# Connector_Exp.net
KiCad netlist of a schematic drawn in EAGLE
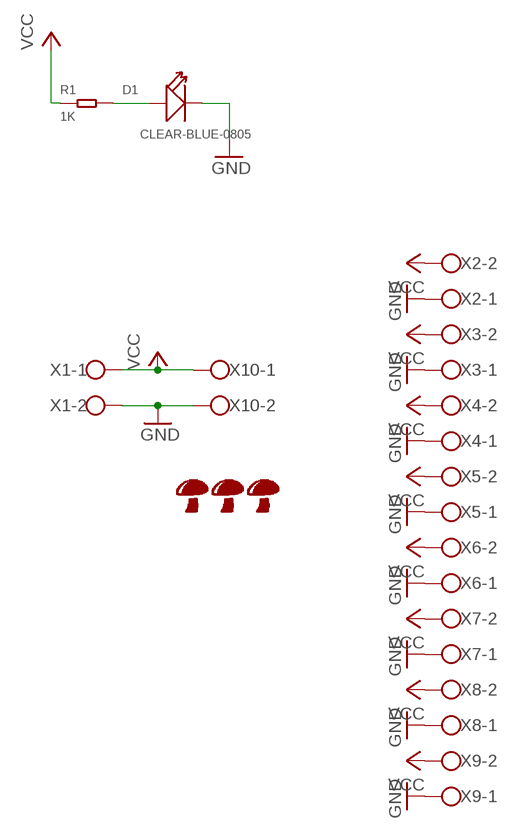
[diagram p0: schematic, sheet 1]

(export (version "E")
  (design (tool "Eeschema 10.0.6"))
  (components
    (comp (ref "D1")
      (value "CLEAR-BLUE-0805")
      (footprint "eagle-import:LED-0805")
      (fields (field (name "MPN") "EL-17-215/BHC-AN1P2/3T"))
      (libsource (lib "eagle-import") (part "SMD-LED-CLEAR-BLUE(0805)"))
    )
    (comp (ref "R1")
      (value "1K")
      (footprint "eagle-import:R0805")
      (fields (field (name "MPN") "RC0805JR-071KL"))
      (libsource (lib "eagle-import") (part "SMD-RES-1K-5%-1/8W(0805)"))
    )
    (comp (ref "U$1")
      (value "SHROOMTOPSILK")
      (footprint "eagle-import:SHROOM_TS")
      (libsource (lib "eagle-import") (part "SHROOMTOPSILK"))
    )
    (comp (ref "U$2")
      (value "SHROOMBOTTOMSILK")
      (footprint "eagle-import:SHROOM_BS")
      (libsource (lib "eagle-import") (part "SHROOMBOTTOMSILK"))
    )
    (comp (ref "U$3")
      (value "SHROOM10MM")
      (footprint "eagle-import:SHROOM10MM")
      (libsource (lib "eagle-import") (part "SHROOM10MM"))
    )
    (comp (ref "X1")
      (value "W237-102")
      (footprint "eagle-import:W237-102")
      (fields (field (name "MPN") "237-102"))
      (libsource (lib "eagle-import") (part "W237-102"))
    )
    (comp (ref "X2")
      (value "W237-102")
      (footprint "eagle-import:W237-102")
      (fields (field (name "MPN") "237-102"))
      (libsource (lib "eagle-import") (part "W237-102"))
    )
    (comp (ref "X3")
      (value "W237-102")
      (footprint "eagle-import:W237-102")
      (fields (field (name "MPN") "237-102"))
      (libsource (lib "eagle-import") (part "W237-102"))
    )
    (comp (ref "X4")
      (value "W237-102")
      (footprint "eagle-import:W237-102")
      (fields (field (name "MPN") "237-102"))
      (libsource (lib "eagle-import") (part "W237-102"))
    )
    (comp (ref "X5")
      (value "W237-102")
      (footprint "eagle-import:W237-102")
      (fields (field (name "MPN") "237-102"))
      (libsource (lib "eagle-import") (part "W237-102"))
    )
    (comp (ref "X6")
      (value "W237-102")
      (footprint "eagle-import:W237-102")
      (fields (field (name "MPN") "237-102"))
      (libsource (lib "eagle-import") (part "W237-102"))
    )
    (comp (ref "X7")
      (value "W237-102")
      (footprint "eagle-import:W237-102")
      (fields (field (name "MPN") "237-102"))
      (libsource (lib "eagle-import") (part "W237-102"))
    )
    (comp (ref "X8")
      (value "W237-102")
      (footprint "eagle-import:W237-102")
      (fields (field (name "MPN") "237-102"))
      (libsource (lib "eagle-import") (part "W237-102"))
    )
    (comp (ref "X9")
      (value "W237-102")
      (footprint "eagle-import:W237-102")
      (fields (field (name "MPN") "237-102"))
      (libsource (lib "eagle-import") (part "W237-102"))
    )
    (comp (ref "X10")
      (value "W237-102")
      (footprint "eagle-import:W237-102")
      (fields (field (name "MPN") "237-102"))
      (libsource (lib "eagle-import") (part "W237-102"))
    )
  )
  (nets
    (net (code "1") (name "GND") (class "Default")
      (node (ref "D1") (pin "-") (pinfunction "-_-") (pintype "passive"))
      (node (ref "X1") (pin "2") (pinfunction "KL_2") (pintype "passive"))
      (node (ref "X10") (pin "2") (pinfunction "KL_2") (pintype "passive"))
      (node (ref "X2") (pin "1") (pinfunction "KL_1") (pintype "passive"))
      (node (ref "X3") (pin "1") (pinfunction "KL_1") (pintype "passive"))
      (node (ref "X4") (pin "1") (pinfunction "KL_1") (pintype "passive"))
      (node (ref "X5") (pin "1") (pinfunction "KL_1") (pintype "passive"))
      (node (ref "X6") (pin "1") (pinfunction "KL_1") (pintype "passive"))
      (node (ref "X7") (pin "1") (pinfunction "KL_1") (pintype "passive"))
      (node (ref "X8") (pin "1") (pinfunction "KL_1") (pintype "passive"))
      (node (ref "X9") (pin "1") (pinfunction "KL_1") (pintype "passive"))
    )
    (net (code "2") (name "Net-(D1-Pad+)") (class "Default")
      (node (ref "D1") (pin "+") (pinfunction "+_+") (pintype "passive"))
      (node (ref "R1") (pin "2") (pinfunction "2_2") (pintype "passive"))
    )
    (net (code "3") (name "VCC") (class "Default")
      (node (ref "R1") (pin "1") (pinfunction "1_1") (pintype "passive"))
      (node (ref "X1") (pin "1") (pinfunction "KL_1") (pintype "passive"))
      (node (ref "X10") (pin "1") (pinfunction "KL_1") (pintype "passive"))
      (node (ref "X2") (pin "2") (pinfunction "KL_2") (pintype "passive"))
      (node (ref "X3") (pin "2") (pinfunction "KL_2") (pintype "passive"))
      (node (ref "X4") (pin "2") (pinfunction "KL_2") (pintype "passive"))
      (node (ref "X5") (pin "2") (pinfunction "KL_2") (pintype "passive"))
      (node (ref "X6") (pin "2") (pinfunction "KL_2") (pintype "passive"))
      (node (ref "X7") (pin "2") (pinfunction "KL_2") (pintype "passive"))
      (node (ref "X8") (pin "2") (pinfunction "KL_2") (pintype "passive"))
      (node (ref "X9") (pin "2") (pinfunction "KL_2") (pintype "passive"))
    )
  )
)
